# ESP32_Meteorologia_MTE_AV_2.net
KiCad netlist of a schematic drawn in EAGLE
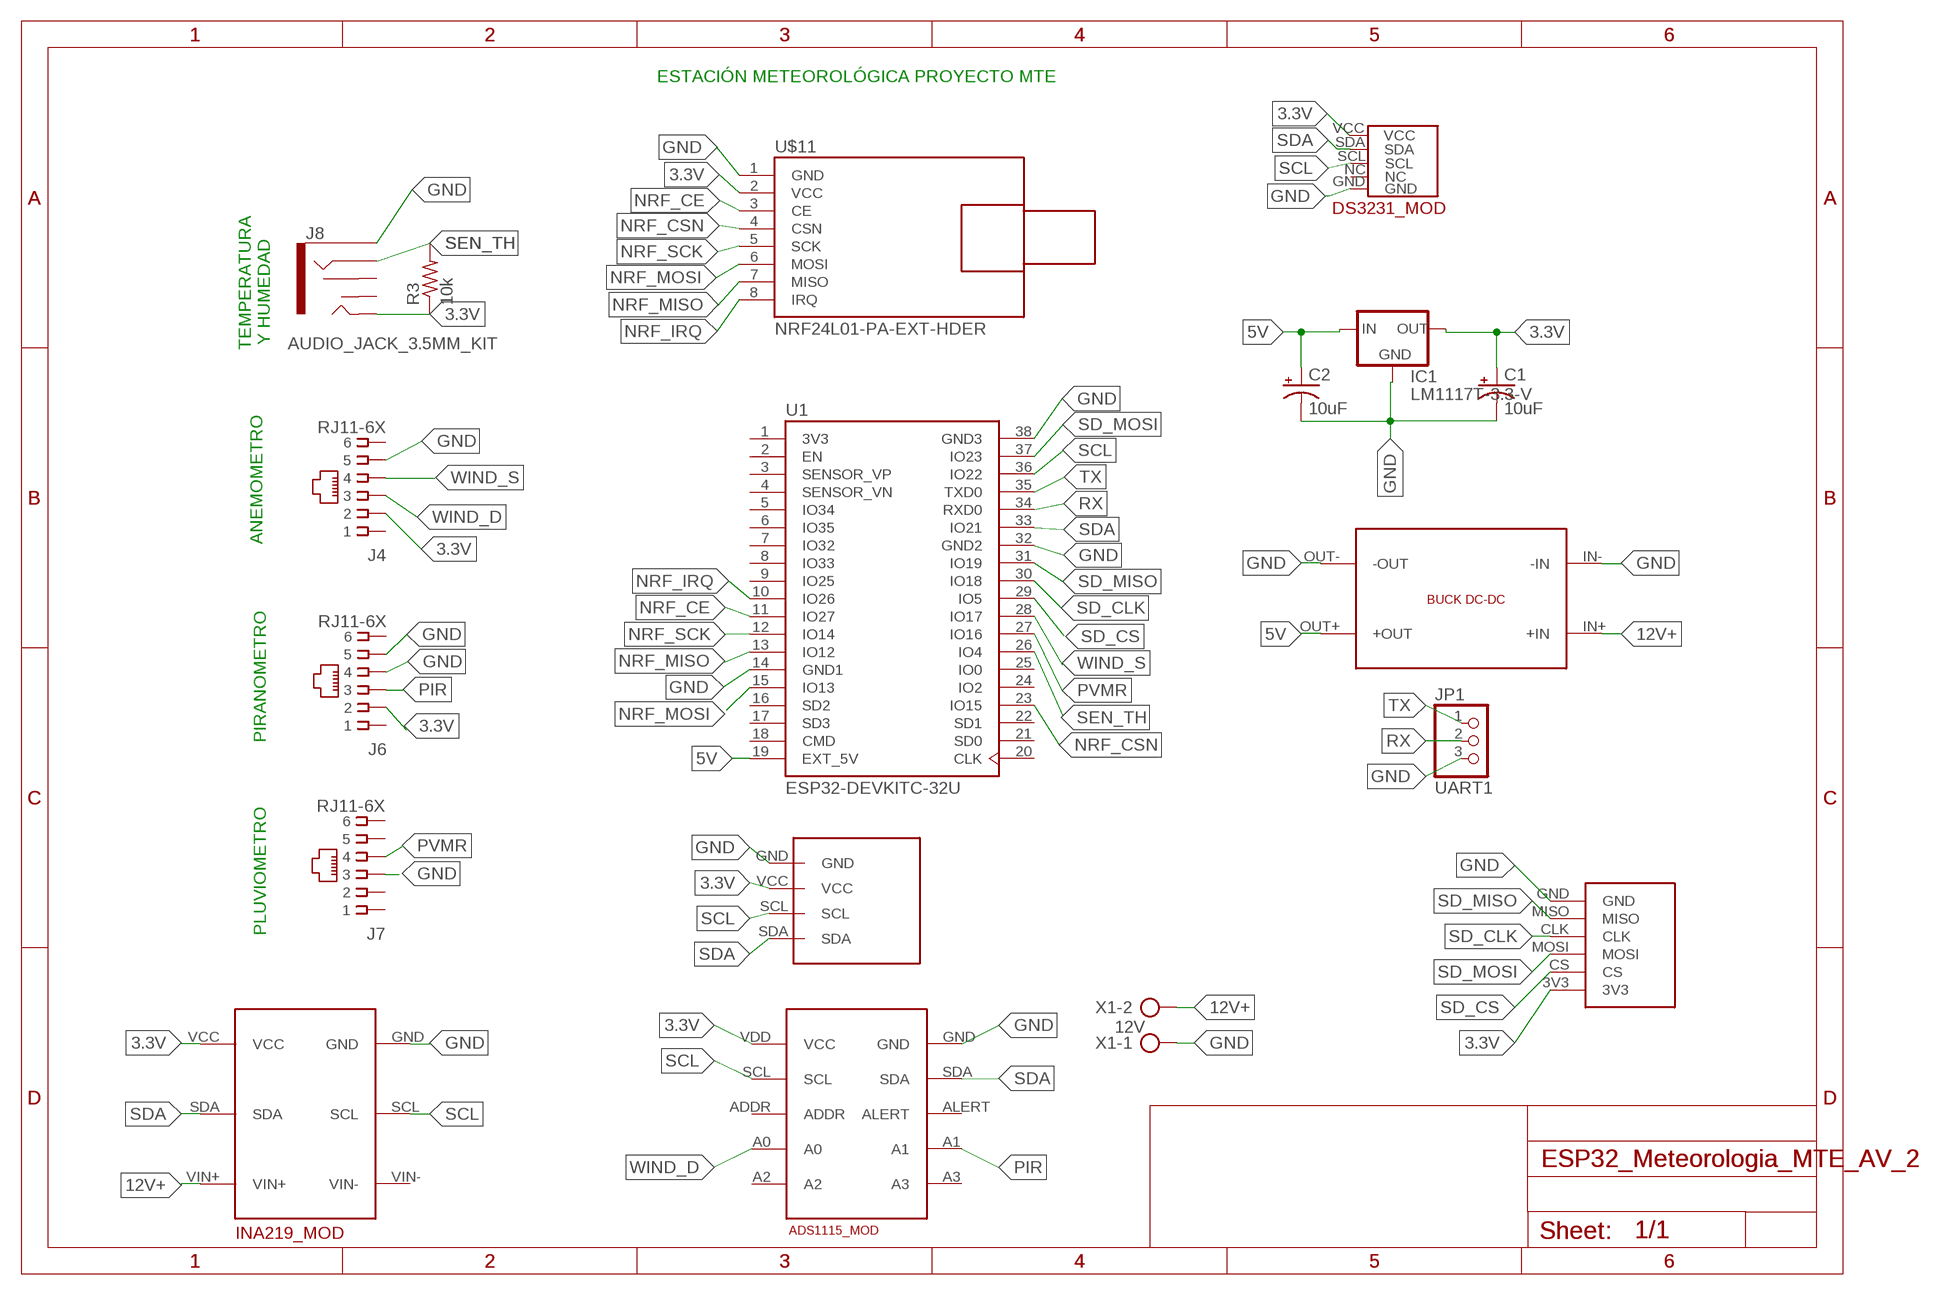
[diagram p0: schematic, sheet 1]

(export (version "E")
  (design (tool "Eeschema 10.0.6"))
  (components
    (comp (ref "C1")
      (value "10uF")
      (footprint "eagle-import:CPOL-RADIAL-2.5MM-5MM")
      (libsource (lib "eagle-import") (part "10UF-POLAR-RADIAL-2.5MM-25V-20%"))
    )
    (comp (ref "C2")
      (value "10uF")
      (footprint "eagle-import:CPOL-RADIAL-2.5MM-5MM")
      (libsource (lib "eagle-import") (part "10UF-POLAR-RADIAL-2.5MM-25V-20%"))
    )
    (comp (ref "IC1")
      (value "LM1117T-3.3-V")
      (footprint "eagle-import:TO220V")
      (libsource (lib "eagle-import") (part "LM1117T--V3.3"))
    )
    (comp (ref "J4")
      (value "RJ11-6X")
      (footprint "eagle-import:RJ11-NO_SHIELD")
      (libsource (lib "eagle-import") (part "RJ11-6X"))
    )
    (comp (ref "J6")
      (value "RJ11-6X")
      (footprint "eagle-import:RJ11-NO_SHIELD")
      (libsource (lib "eagle-import") (part "RJ11-6X"))
    )
    (comp (ref "J7")
      (value "RJ11-6X")
      (footprint "eagle-import:RJ11-NO_SHIELD")
      (libsource (lib "eagle-import") (part "RJ11-6X"))
    )
    (comp (ref "J8")
      (value "AUDIO_JACK_3.5MM_KIT")
      (footprint "eagle-import:AUDIO-JACK-KIT")
      (libsource (lib "eagle-import") (part "AUDIO_JACK_3.5MM_KIT"))
    )
    (comp (ref "JP1")
      (value "UART1")
      (footprint "eagle-import:1X03")
      (libsource (lib "eagle-import") (part "PINHD-1X3"))
    )
    (comp (ref "R3")
      (value "10k")
      (footprint "eagle-import:0207_10")
      (libsource (lib "eagle-import") (part "R-US_0207/10"))
    )
    (comp (ref "U$1")
      (value "ADS1115_BIG")
      (footprint "eagle-import:ADS1115_BIG")
      (libsource (lib "eagle-import") (part "ADS1115_BIG"))
    )
    (comp (ref "U$2")
      (value "MODULO_MSD2")
      (footprint "eagle-import:MICROSD-BREAKOUT")
      (libsource (lib "eagle-import") (part "MODULO_MSD2"))
    )
    (comp (ref "U$7")
      (value "INA219_MOD_HDR")
      (footprint "eagle-import:INA219_MOD_HDR")
      (libsource (lib "eagle-import") (part "INA219_MOD_HDR"))
    )
    (comp (ref "U$8")
      (value "BUCK_LM2596")
      (footprint "eagle-import:BUCK_LM2596")
      (libsource (lib "eagle-import") (part "BUCK_LM2596"))
    )
    (comp (ref "U$10")
      (value "DS3231_MOD")
      (footprint "eagle-import:DS3231_MOD")
      (libsource (lib "eagle-import") (part "DS3231_MOD"))
    )
    (comp (ref "U$11")
      (value "NRF24L01-PA-EXT-HDER")
      (footprint "eagle-import:NRF24L01-HEADER")
      (libsource (lib "eagle-import") (part "NRF24L01-PA-EXT-HDER"))
    )
    (comp (ref "U$12")
      (value "OLED_I2C_096")
      (footprint "eagle-import:OLED_096_I2C")
      (libsource (lib "eagle-import") (part "OLED_I2C_096"))
    )
    (comp (ref "U1")
      (value "ESP32-DEVKITC-32U")
      (footprint "eagle-import:MODULE_ESP32-DEVKITC-32U")
      (fields (field (name "MF") "Espressif Systems"))
      (libsource (lib "eagle-import") (part "ESP32-DEVKITC-32U"))
    )
    (comp (ref "X1")
      (value "12V")
      (footprint "eagle-import:AK500_2")
      (libsource (lib "eagle-import") (part "AK500/2"))
    )
  )
  (nets
    (net (code "1") (name "/3V3") (class "Default")
      (node (ref "U1") (pin "1") (pinfunction "3V3_1") (pintype "power_in"))
    )
    (net (code "2") (name "3.3V") (class "Default")
      (node (ref "C1") (pin "1") (pinfunction "+_1") (pintype "passive"))
      (node (ref "IC1") (pin "2") (pinfunction "OUT_2") (pintype "passive"))
      (node (ref "J4") (pin "2") (pinfunction "2_2") (pintype "passive"))
      (node (ref "J6") (pin "2") (pinfunction "2_2") (pintype "passive"))
      (node (ref "J8") (pin "TIP") (pinfunction "TIP_TIP") (pintype "bidirectional"))
      (node (ref "R3") (pin "1") (pinfunction "1_1") (pintype "passive"))
      (node (ref "U$1") (pin "VDD") (pinfunction "VCC_VDD") (pintype "bidirectional"))
      (node (ref "U$10") (pin "VCC") (pinfunction "VCC_VCC") (pintype "bidirectional"))
      (node (ref "U$11") (pin "2") (pinfunction "VCC_2") (pintype "power_in"))
      (node (ref "U$12") (pin "VCC") (pinfunction "VCC_VCC") (pintype "power_in"))
      (node (ref "U$2") (pin "3V3") (pinfunction "3V3_3V3") (pintype "bidirectional"))
      (node (ref "U$7") (pin "VCC") (pinfunction "VCC_VCC") (pintype "bidirectional"))
    )
    (net (code "3") (name "5V") (class "Default")
      (node (ref "C2") (pin "1") (pinfunction "+_1") (pintype "passive"))
      (node (ref "IC1") (pin "3") (pinfunction "IN_3") (pintype "input"))
      (node (ref "U$8") (pin "OUT+") (pinfunction "+OUT_OUT+") (pintype "bidirectional"))
      (node (ref "U1") (pin "19") (pinfunction "EXT_5V_19") (pintype "power_in"))
    )
    (net (code "4") (name "12V+") (class "Default")
      (node (ref "U$7") (pin "VIN+") (pinfunction "VIN+_VIN+") (pintype "bidirectional"))
      (node (ref "U$8") (pin "IN+") (pinfunction "+IN_IN+") (pintype "bidirectional"))
      (node (ref "X1") (pin "2") (pinfunction "KL_2") (pintype "passive"))
    )
    (net (code "5") (name "GND") (class "Default")
      (node (ref "C1") (pin "2") (pinfunction "-_2") (pintype "passive"))
      (node (ref "C2") (pin "2") (pinfunction "-_2") (pintype "passive"))
      (node (ref "IC1") (pin "1") (pinfunction "GND_1") (pintype "input"))
      (node (ref "J4") (pin "5") (pinfunction "5_5") (pintype "passive"))
      (node (ref "J6") (pin "4") (pinfunction "4_4") (pintype "passive"))
      (node (ref "J6") (pin "5") (pinfunction "5_5") (pintype "passive"))
      (node (ref "J7") (pin "3") (pinfunction "3_3") (pintype "passive"))
      (node (ref "J8") (pin "SLEEVE") (pinfunction "SLEEVE_SLEEVE") (pintype "bidirectional"))
      (node (ref "JP1") (pin "3") (pinfunction "3_3") (pintype "passive"))
      (node (ref "U$1") (pin "GND") (pinfunction "GND_GND") (pintype "bidirectional"))
      (node (ref "U$10") (pin "GND") (pinfunction "GND_GND") (pintype "bidirectional"))
      (node (ref "U$11") (pin "1") (pinfunction "GND_1") (pintype "power_in"))
      (node (ref "U$12") (pin "GND") (pinfunction "GND_GND") (pintype "power_in"))
      (node (ref "U$2") (pin "GND") (pinfunction "GND_GND") (pintype "bidirectional"))
      (node (ref "U$7") (pin "GND") (pinfunction "GND_GND") (pintype "bidirectional"))
      (node (ref "U$8") (pin "IN-") (pinfunction "-IN_IN-") (pintype "bidirectional"))
      (node (ref "U$8") (pin "OUT-") (pinfunction "-OUT_OUT-") (pintype "bidirectional"))
      (node (ref "U1") (pin "14") (pinfunction "GND1_14") (pintype "power_in"))
      (node (ref "U1") (pin "32") (pinfunction "GND2_32") (pintype "power_in"))
      (node (ref "U1") (pin "38") (pinfunction "GND3_38") (pintype "power_in"))
      (node (ref "X1") (pin "1") (pinfunction "KL_1") (pintype "passive"))
    )
    (net (code "6") (name "NRF_CE") (class "Default")
      (node (ref "U$11") (pin "3") (pinfunction "CE_3") (pintype "bidirectional"))
      (node (ref "U1") (pin "11") (pinfunction "IO27_11") (pintype "bidirectional"))
    )
    (net (code "7") (name "NRF_CSN") (class "Default")
      (node (ref "U$11") (pin "4") (pinfunction "CSN_4") (pintype "bidirectional"))
      (node (ref "U1") (pin "23") (pinfunction "IO15_23") (pintype "bidirectional"))
    )
    (net (code "8") (name "NRF_IRQ") (class "Default")
      (node (ref "U$11") (pin "8") (pinfunction "IRQ_8") (pintype "bidirectional"))
      (node (ref "U1") (pin "10") (pinfunction "IO26_10") (pintype "bidirectional"))
    )
    (net (code "9") (name "NRF_MISO") (class "Default")
      (node (ref "U$11") (pin "7") (pinfunction "MISO_7") (pintype "bidirectional"))
      (node (ref "U1") (pin "13") (pinfunction "IO12_13") (pintype "bidirectional"))
    )
    (net (code "10") (name "NRF_MOSI") (class "Default")
      (node (ref "U$11") (pin "6") (pinfunction "MOSI_6") (pintype "bidirectional"))
      (node (ref "U1") (pin "15") (pinfunction "IO13_15") (pintype "bidirectional"))
    )
    (net (code "11") (name "NRF_SCK") (class "Default")
      (node (ref "U$11") (pin "5") (pinfunction "SCK_5") (pintype "bidirectional"))
      (node (ref "U1") (pin "12") (pinfunction "IO14_12") (pintype "bidirectional"))
    )
    (net (code "12") (name "PIR") (class "Default")
      (node (ref "J6") (pin "3") (pinfunction "3_3") (pintype "passive"))
      (node (ref "U$1") (pin "A1") (pinfunction "A1_A1") (pintype "bidirectional"))
    )
    (net (code "13") (name "PVMR") (class "Default")
      (node (ref "J7") (pin "4") (pinfunction "4_4") (pintype "passive"))
      (node (ref "U1") (pin "27") (pinfunction "IO16_27") (pintype "bidirectional"))
    )
    (net (code "14") (name "RX") (class "Default")
      (node (ref "JP1") (pin "2") (pinfunction "2_2") (pintype "passive"))
      (node (ref "U1") (pin "34") (pinfunction "RXD0_34") (pintype "input"))
    )
    (net (code "15") (name "SCL") (class "Default")
      (node (ref "U$1") (pin "SCL") (pinfunction "SCL_SCL") (pintype "bidirectional"))
      (node (ref "U$10") (pin "SCL") (pinfunction "SCL_SCL") (pintype "bidirectional"))
      (node (ref "U$12") (pin "SCL") (pinfunction "SCL_SCL") (pintype "bidirectional"))
      (node (ref "U$7") (pin "SCL") (pinfunction "SCL_SCL") (pintype "bidirectional"))
      (node (ref "U1") (pin "36") (pinfunction "IO22_36") (pintype "bidirectional"))
    )
    (net (code "16") (name "SDA") (class "Default")
      (node (ref "U$1") (pin "SDA") (pinfunction "SDA_SDA") (pintype "bidirectional"))
      (node (ref "U$10") (pin "SDA") (pinfunction "SDA_SDA") (pintype "bidirectional"))
      (node (ref "U$12") (pin "SDA") (pinfunction "SDA_SDA") (pintype "bidirectional"))
      (node (ref "U$7") (pin "SDA") (pinfunction "SDA_SDA") (pintype "bidirectional"))
      (node (ref "U1") (pin "33") (pinfunction "IO21_33") (pintype "bidirectional"))
    )
    (net (code "17") (name "SD_CLK") (class "Default")
      (node (ref "U$2") (pin "CLK") (pinfunction "CLK_CLK") (pintype "bidirectional"))
      (node (ref "U1") (pin "30") (pinfunction "IO18_30") (pintype "bidirectional"))
    )
    (net (code "18") (name "SD_CS") (class "Default")
      (node (ref "U$2") (pin "CS") (pinfunction "CS_CS") (pintype "bidirectional"))
      (node (ref "U1") (pin "29") (pinfunction "IO5_29") (pintype "bidirectional"))
    )
    (net (code "19") (name "SD_MISO") (class "Default")
      (node (ref "U$2") (pin "MISO") (pinfunction "MISO_MISO") (pintype "bidirectional"))
      (node (ref "U1") (pin "31") (pinfunction "IO19_31") (pintype "bidirectional"))
    )
    (net (code "20") (name "SD_MOSI") (class "Default")
      (node (ref "U$2") (pin "MOSI") (pinfunction "MOSI_MOSI") (pintype "bidirectional"))
      (node (ref "U1") (pin "37") (pinfunction "IO23_37") (pintype "bidirectional"))
    )
    (net (code "21") (name "SEN_TH") (class "Default")
      (node (ref "J8") (pin "RING") (pinfunction "RING_RING") (pintype "bidirectional"))
      (node (ref "R3") (pin "2") (pinfunction "2_2") (pintype "passive"))
      (node (ref "U1") (pin "26") (pinfunction "IO4_26") (pintype "bidirectional"))
    )
    (net (code "22") (name "TX") (class "Default")
      (node (ref "JP1") (pin "1") (pinfunction "1_1") (pintype "passive"))
      (node (ref "U1") (pin "35") (pinfunction "TXD0_35") (pintype "output"))
    )
    (net (code "23") (name "WIND_D") (class "Default")
      (node (ref "J4") (pin "3") (pinfunction "3_3") (pintype "passive"))
      (node (ref "U$1") (pin "A0") (pinfunction "A0_A0") (pintype "bidirectional"))
    )
    (net (code "24") (name "WIND_S") (class "Default")
      (node (ref "J4") (pin "4") (pinfunction "4_4") (pintype "passive"))
      (node (ref "U1") (pin "28") (pinfunction "IO17_28") (pintype "bidirectional"))
    )
    (net (code "25") (name "unconnected-(J4-Pad1)") (class "Default")
      (node (ref "J4") (pin "1") (pinfunction "1_1") (pintype "passive"))
    )
    (net (code "26") (name "unconnected-(J4-Pad6)") (class "Default")
      (node (ref "J4") (pin "6") (pinfunction "6_6") (pintype "passive"))
    )
    (net (code "27") (name "unconnected-(J6-Pad1)") (class "Default")
      (node (ref "J6") (pin "1") (pinfunction "1_1") (pintype "passive"))
    )
    (net (code "28") (name "unconnected-(J6-Pad6)") (class "Default")
      (node (ref "J6") (pin "6") (pinfunction "6_6") (pintype "passive"))
    )
    (net (code "29") (name "unconnected-(J7-Pad1)") (class "Default")
      (node (ref "J7") (pin "1") (pinfunction "1_1") (pintype "passive"))
    )
    (net (code "30") (name "unconnected-(J7-Pad2)") (class "Default")
      (node (ref "J7") (pin "2") (pinfunction "2_2") (pintype "passive"))
    )
    (net (code "31") (name "unconnected-(J7-Pad5)") (class "Default")
      (node (ref "J7") (pin "5") (pinfunction "5_5") (pintype "passive"))
    )
    (net (code "32") (name "unconnected-(J7-Pad6)") (class "Default")
      (node (ref "J7") (pin "6") (pinfunction "6_6") (pintype "passive"))
    )
    (net (code "33") (name "unconnected-(J8-PadRSH)") (class "Default")
      (node (ref "J8") (pin "RSH") (pinfunction "RSH_RSH") (pintype "bidirectional"))
    )
    (net (code "34") (name "unconnected-(J8-PadTSH)") (class "Default")
      (node (ref "J8") (pin "TSH") (pinfunction "TSH_TSH") (pintype "bidirectional"))
    )
    (net (code "35") (name "unconnected-(U$1-PadA2)") (class "Default")
      (node (ref "U$1") (pin "A2") (pinfunction "A2_A2") (pintype "bidirectional"))
    )
    (net (code "36") (name "unconnected-(U$1-PadA3)") (class "Default")
      (node (ref "U$1") (pin "A3") (pinfunction "A3_A3") (pintype "bidirectional"))
    )
    (net (code "37") (name "unconnected-(U$1-PadADDR)") (class "Default")
      (node (ref "U$1") (pin "ADDR") (pinfunction "ADDR_ADDR") (pintype "bidirectional"))
    )
    (net (code "38") (name "unconnected-(U$1-PadALERT)") (class "Default")
      (node (ref "U$1") (pin "ALERT") (pinfunction "ALERT_ALERT") (pintype "bidirectional"))
    )
    (net (code "39") (name "unconnected-(U$7-PadVIN-)") (class "Default")
      (node (ref "U$7") (pin "VIN-") (pinfunction "VIN-_VIN-") (pintype "bidirectional"))
    )
    (net (code "40") (name "unconnected-(U$10-PadNC)") (class "Default")
      (node (ref "U$10") (pin "NC") (pinfunction "NC_NC") (pintype "bidirectional"))
    )
    (net (code "41") (name "unconnected-(U1-CLK-Pad20)") (class "Default")
      (node (ref "U1") (pin "20") (pinfunction "CLK_20") (pintype "input"))
    )
    (net (code "42") (name "unconnected-(U1-CMD-Pad18)") (class "Default")
      (node (ref "U1") (pin "18") (pinfunction "CMD_18") (pintype "bidirectional"))
    )
    (net (code "43") (name "unconnected-(U1-EN-Pad2)") (class "Default")
      (node (ref "U1") (pin "2") (pinfunction "EN_2") (pintype "input"))
    )
    (net (code "44") (name "unconnected-(U1-IO0-Pad25)") (class "Default")
      (node (ref "U1") (pin "25") (pinfunction "IO0_25") (pintype "bidirectional"))
    )
    (net (code "45") (name "unconnected-(U1-IO2-Pad24)") (class "Default")
      (node (ref "U1") (pin "24") (pinfunction "IO2_24") (pintype "bidirectional"))
    )
    (net (code "46") (name "unconnected-(U1-IO25-Pad9)") (class "Default")
      (node (ref "U1") (pin "9") (pinfunction "IO25_9") (pintype "bidirectional"))
    )
    (net (code "47") (name "unconnected-(U1-IO32-Pad7)") (class "Default")
      (node (ref "U1") (pin "7") (pinfunction "IO32_7") (pintype "bidirectional"))
    )
    (net (code "48") (name "unconnected-(U1-IO33-Pad8)") (class "Default")
      (node (ref "U1") (pin "8") (pinfunction "IO33_8") (pintype "bidirectional"))
    )
    (net (code "49") (name "unconnected-(U1-IO34-Pad5)") (class "Default")
      (node (ref "U1") (pin "5") (pinfunction "IO34_5") (pintype "bidirectional"))
    )
    (net (code "50") (name "unconnected-(U1-IO35-Pad6)") (class "Default")
      (node (ref "U1") (pin "6") (pinfunction "IO35_6") (pintype "bidirectional"))
    )
    (net (code "51") (name "unconnected-(U1-SD0-Pad21)") (class "Default")
      (node (ref "U1") (pin "21") (pinfunction "SD0_21") (pintype "bidirectional"))
    )
    (net (code "52") (name "unconnected-(U1-SD1-Pad22)") (class "Default")
      (node (ref "U1") (pin "22") (pinfunction "SD1_22") (pintype "bidirectional"))
    )
    (net (code "53") (name "unconnected-(U1-SD2-Pad16)") (class "Default")
      (node (ref "U1") (pin "16") (pinfunction "SD2_16") (pintype "bidirectional"))
    )
    (net (code "54") (name "unconnected-(U1-SD3-Pad17)") (class "Default")
      (node (ref "U1") (pin "17") (pinfunction "SD3_17") (pintype "bidirectional"))
    )
    (net (code "55") (name "unconnected-(U1-SENSOR_VN-Pad4)") (class "Default")
      (node (ref "U1") (pin "4") (pinfunction "SENSOR_VN_4") (pintype "input"))
    )
    (net (code "56") (name "unconnected-(U1-SENSOR_VP-Pad3)") (class "Default")
      (node (ref "U1") (pin "3") (pinfunction "SENSOR_VP_3") (pintype "input"))
    )
  )
)
